# Main.net
KiCad netlist of a schematic drawn in EAGLE
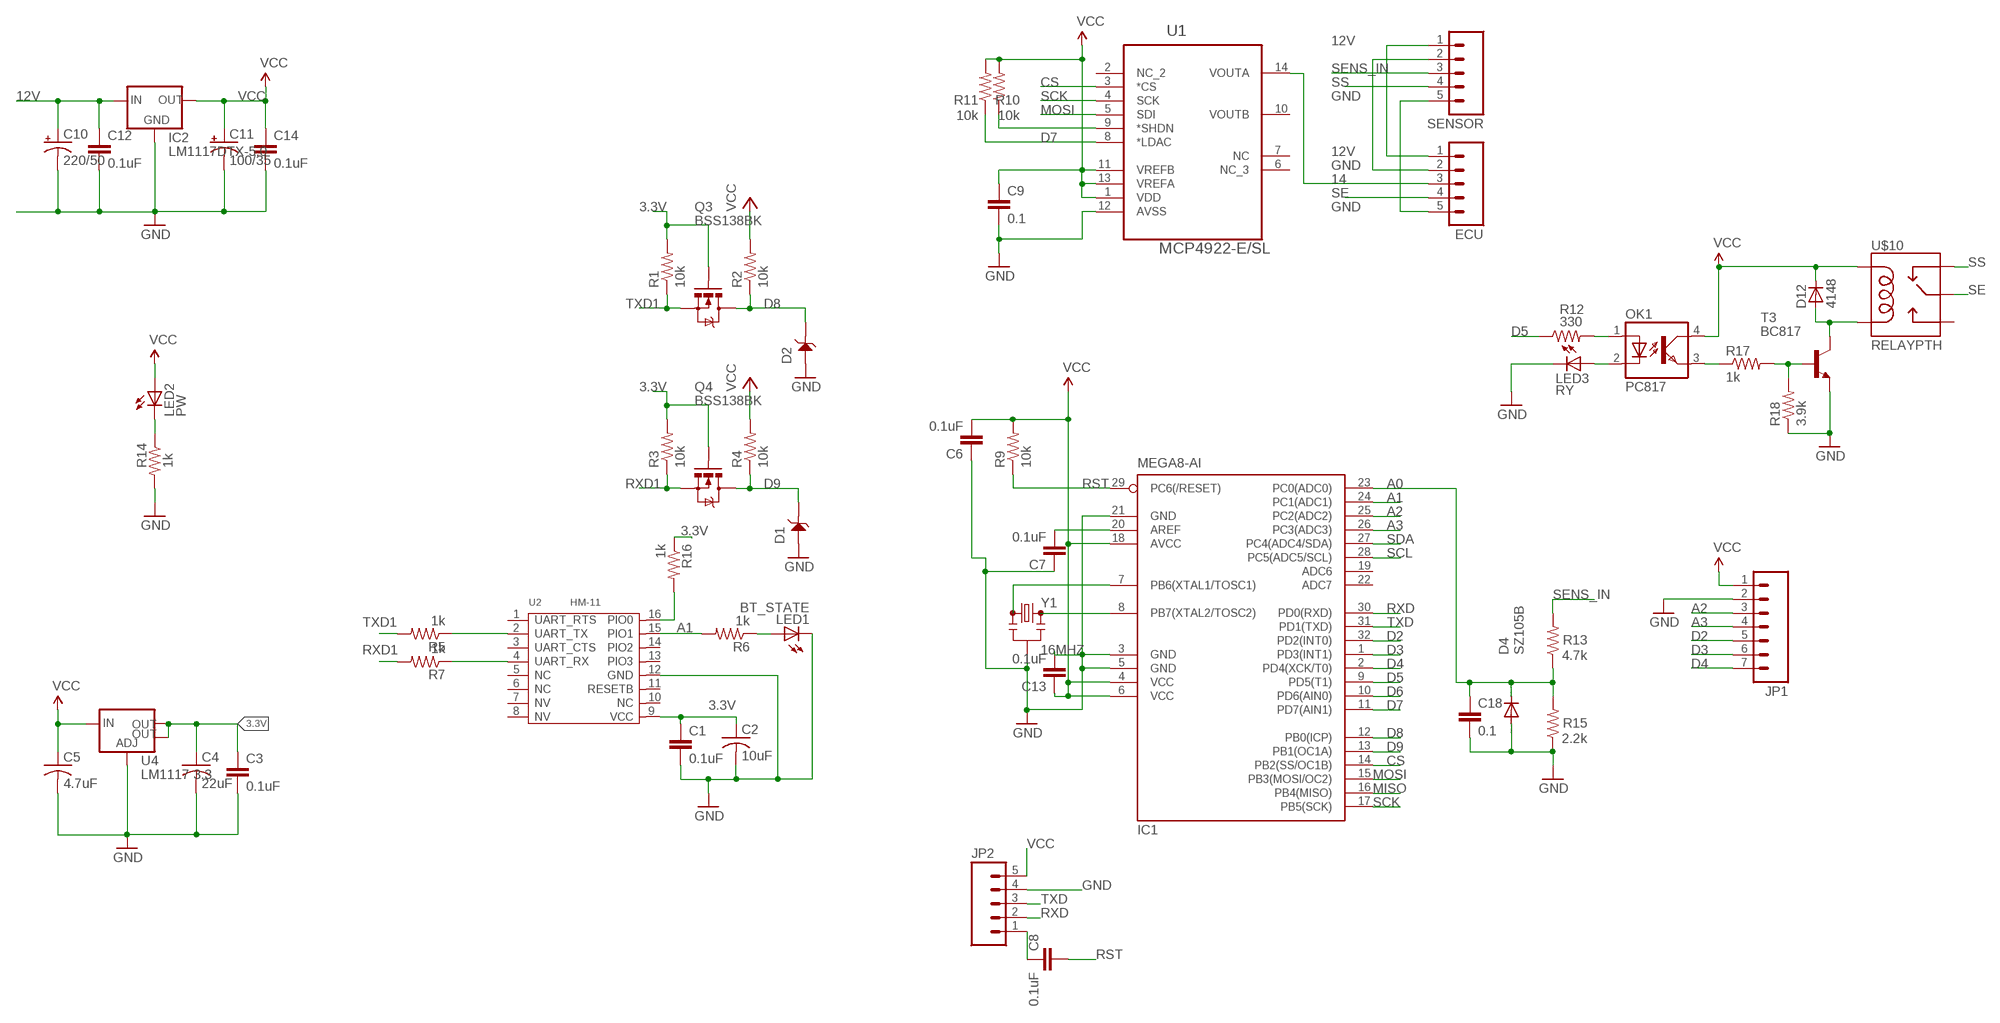
[diagram p0: schematic, sheet 1]

(export (version "E")
  (design (tool "Eeschema 10.0.6"))
  (components
    (comp (ref "C1")
      (value "0.1uF")
      (footprint "eagle-import:0805")
      (libsource (lib "eagle-import") (part "CAP0805"))
    )
    (comp (ref "C2")
      (value "10uF")
      (footprint "eagle-import:C1206")
      (libsource (lib "eagle-import") (part "C-USC1206"))
    )
    (comp (ref "C3")
      (value "0.1uF")
      (footprint "eagle-import:0805")
      (libsource (lib "eagle-import") (part "SparkFun-Passives_CAP0805"))
    )
    (comp (ref "C4")
      (value "22uF")
      (footprint "eagle-import:C1206")
      (libsource (lib "eagle-import") (part "C-USC1206"))
    )
    (comp (ref "C5")
      (value "4.7uF")
      (footprint "eagle-import:C1206")
      (libsource (lib "eagle-import") (part "C-USC1206"))
    )
    (comp (ref "C6")
      (value "0.1uF")
      (footprint "eagle-import:0805")
      (libsource (lib "eagle-import") (part "SparkFun-Passives_CAP0805"))
    )
    (comp (ref "C7")
      (value "0.1uF")
      (footprint "eagle-import:0805")
      (libsource (lib "eagle-import") (part "SparkFun-Passives_CAP0805"))
    )
    (comp (ref "C8")
      (value "0.1uF")
      (footprint "eagle-import:0805")
      (libsource (lib "eagle-import") (part "SparkFun-Passives_CAP0805"))
    )
    (comp (ref "C9")
      (value "0.1")
      (footprint "eagle-import:0805")
      (libsource (lib "eagle-import") (part "SparkFun-Passives_CAP0805"))
    )
    (comp (ref "C10")
      (value "220/50")
      (footprint "eagle-import:153CLV-1010")
      (libsource (lib "eagle-import") (part "CPOL-US153CLV-1010"))
    )
    (comp (ref "C11")
      (value "100/35")
      (footprint "eagle-import:153CLV-0605")
      (libsource (lib "eagle-import") (part "CPOL-US153CLV-0605"))
    )
    (comp (ref "C12")
      (value "0.1uF")
      (footprint "eagle-import:0805")
      (libsource (lib "eagle-import") (part "SparkFun-Passives_CAP0805"))
    )
    (comp (ref "C13")
      (value "0.1uF")
      (footprint "eagle-import:0805")
      (libsource (lib "eagle-import") (part "SparkFun-Passives_CAP0805"))
    )
    (comp (ref "C14")
      (value "0.1uF")
      (footprint "eagle-import:0805")
      (libsource (lib "eagle-import") (part "SparkFun-Passives_CAP0805"))
    )
    (comp (ref "C18")
      (value "0.1")
      (footprint "eagle-import:0805")
      (libsource (lib "eagle-import") (part "SparkFun-Passives_CAP0805"))
    )
    (comp (ref "D1")
      (value "SMF5.0A")
      (footprint "eagle-import:SOD123-2.7X1.6")
      (libsource (lib "eagle-import") (part "D-ESD-2P'CESD5V0D1'"))
    )
    (comp (ref "D2")
      (value "SMF5.0A")
      (footprint "eagle-import:SOD123-2.7X1.6")
      (libsource (lib "eagle-import") (part "D-ESD-2P'CESD5V0D1'"))
    )
    (comp (ref "D4")
      (value "SZ105B")
      (footprint "eagle-import:DO-214AC")
      (libsource (lib "eagle-import") (part "DIODE-DO-214AC"))
    )
    (comp (ref "D12")
      (value "4148")
      (footprint "eagle-import:SOD80")
      (libsource (lib "eagle-import") (part "D-SOD-80"))
    )
    (comp (ref "ECU")
      (value "M05PTH")
      (footprint "eagle-import:1X05")
      (libsource (lib "eagle-import") (part "M05PTH"))
    )
    (comp (ref "IC1")
      (value "MEGA8-AI")
      (footprint "eagle-import:TQFP32-08")
      (fields (field (name "MPN") "ATMEGA8-16AU"))
      (libsource (lib "eagle-import") (part "MEGA8-AI"))
    )
    (comp (ref "IC2")
      (value "LM1117DTX-5.0")
      (footprint "eagle-import:TO252")
      (libsource (lib "eagle-import") (part "LM1117DTX-3.3"))
    )
    (comp (ref "JP1")
      (value "M07")
      (footprint "eagle-import:1X07")
      (libsource (lib "eagle-import") (part "M07"))
    )
    (comp (ref "JP2")
      (value "M05PTH")
      (footprint "eagle-import:1X05")
      (libsource (lib "eagle-import") (part "M05PTH"))
    )
    (comp (ref "LED1")
      (value "BT_STATE")
      (footprint "eagle-import:LED3MM")
      (libsource (lib "eagle-import") (part "LED3MM"))
    )
    (comp (ref "LED2")
      (value "PW")
      (footprint "eagle-import:LED3MM")
      (libsource (lib "eagle-import") (part "LED3MM"))
    )
    (comp (ref "LED3")
      (value "RY")
      (footprint "eagle-import:LED3MM")
      (libsource (lib "eagle-import") (part "LED3MM"))
    )
    (comp (ref "OK1")
      (value "PC817")
      (footprint "eagle-import:DIL4-SMD")
      (libsource (lib "eagle-import") (part "LTV816S"))
    )
    (comp (ref "Q3")
      (value "BSS138BK")
      (footprint "eagle-import:SOT23-3")
      (libsource (lib "eagle-import") (part "MOSFET-NCHANNELBSS138"))
    )
    (comp (ref "Q4")
      (value "BSS138BK")
      (footprint "eagle-import:SOT23-3")
      (libsource (lib "eagle-import") (part "MOSFET-NCHANNELBSS138"))
    )
    (comp (ref "R1")
      (value "10k")
      (footprint "eagle-import:0805")
      (libsource (lib "eagle-import") (part "SparkFun-Resistors_RESISTOR0805-RES"))
    )
    (comp (ref "R2")
      (value "10k")
      (footprint "eagle-import:0805")
      (libsource (lib "eagle-import") (part "SparkFun-Resistors_RESISTOR0805-RES"))
    )
    (comp (ref "R3")
      (value "10k")
      (footprint "eagle-import:0805")
      (libsource (lib "eagle-import") (part "SparkFun-Resistors_RESISTOR0805-RES"))
    )
    (comp (ref "R4")
      (value "10k")
      (footprint "eagle-import:0805")
      (libsource (lib "eagle-import") (part "SparkFun-Resistors_RESISTOR0805-RES"))
    )
    (comp (ref "R5")
      (value "1k")
      (footprint "eagle-import:0805")
      (libsource (lib "eagle-import") (part "SparkFun-Resistors_RESISTOR0805-RES"))
    )
    (comp (ref "R6")
      (value "1k")
      (footprint "eagle-import:0805")
      (libsource (lib "eagle-import") (part "SparkFun-Resistors_RESISTOR0805-RES"))
    )
    (comp (ref "R7")
      (value "1k")
      (footprint "eagle-import:0805")
      (libsource (lib "eagle-import") (part "SparkFun-Resistors_RESISTOR0805-RES"))
    )
    (comp (ref "R9")
      (value "10k")
      (footprint "eagle-import:0805")
      (libsource (lib "eagle-import") (part "SparkFun-Resistors_RESISTOR0805-RES"))
    )
    (comp (ref "R10")
      (value "10k")
      (footprint "eagle-import:0805")
      (libsource (lib "eagle-import") (part "SparkFun-Resistors_RESISTOR0805-RES"))
    )
    (comp (ref "R11")
      (value "10k")
      (footprint "eagle-import:0805")
      (libsource (lib "eagle-import") (part "SparkFun-Resistors_RESISTOR0805-RES"))
    )
    (comp (ref "R12")
      (value "330")
      (footprint "eagle-import:0805")
      (libsource (lib "eagle-import") (part "RESISTOR0805-RES"))
    )
    (comp (ref "R13")
      (value "4.7k")
      (footprint "eagle-import:0805")
      (libsource (lib "eagle-import") (part "SparkFun-Resistors_RESISTOR0805-RES"))
    )
    (comp (ref "R14")
      (value "1k")
      (footprint "eagle-import:0805")
      (libsource (lib "eagle-import") (part "SparkFun-Resistors_RESISTOR0805-RES"))
    )
    (comp (ref "R15")
      (value "2.2k")
      (footprint "eagle-import:0805")
      (libsource (lib "eagle-import") (part "SparkFun-Resistors_RESISTOR0805-RES"))
    )
    (comp (ref "R16")
      (value "1k")
      (footprint "eagle-import:0805")
      (libsource (lib "eagle-import") (part "SparkFun-Resistors_RESISTOR0805-RES"))
    )
    (comp (ref "R17")
      (value "1k")
      (footprint "eagle-import:0805")
      (libsource (lib "eagle-import") (part "RESISTOR0805-RES"))
    )
    (comp (ref "R18")
      (value "3.9k")
      (footprint "eagle-import:0805")
      (libsource (lib "eagle-import") (part "RESISTOR0805-RES"))
    )
    (comp (ref "SENSOR")
      (value "M05PTH")
      (footprint "eagle-import:1X05")
      (libsource (lib "eagle-import") (part "M05PTH"))
    )
    (comp (ref "T3")
      (value "BC817")
      (footprint "eagle-import:SOT23-BEC")
      (libsource (lib "eagle-import") (part "-NPN-SOT23-BECBC817-16"))
    )
    (comp (ref "U$10")
      (value "RELAYPTH")
      (footprint "eagle-import:SRD-05VDC-SL-C")
      (libsource (lib "eagle-import") (part "RELAYPTH"))
    )
    (comp (ref "U1")
      (value "MCP4922-E/SL")
      (footprint "eagle-import:SOIC127P600X175-14N")
      (libsource (lib "eagle-import") (part "MCP4922-E/SL"))
    )
    (comp (ref "U2")
      (value "HM-11")
      (footprint "eagle-import:16P-18.5X13.5X0.8")
      (libsource (lib "eagle-import") (part "HM-11"))
    )
    (comp (ref "U4")
      (value "LM1117 3.3")
      (footprint "eagle-import:SOT223")
      (libsource (lib "eagle-import") (part "V_REG_LM1117SOT223"))
    )
    (comp (ref "Y1")
      (value "16MHZ")
      (footprint "eagle-import:RESONATOR-SMD")
      (libsource (lib "eagle-import") (part "RESONATOR16MHZ"))
    )
  )
  (nets
    (net (code "1") (name "/12V") (class "Default")
      (node (ref "C10") (pin "+") (pinfunction "+_+") (pintype "passive"))
      (node (ref "C12") (pin "1") (pinfunction "1_1") (pintype "passive"))
      (node (ref "ECU") (pin "1") (pinfunction "1_1") (pintype "passive"))
      (node (ref "IC2") (pin "2") (pinfunction "IN_2") (pintype "input"))
      (node (ref "SENSOR") (pin "1") (pinfunction "1_1") (pintype "passive"))
    )
    (net (code "2") (name "/14") (class "Default")
      (node (ref "ECU") (pin "3") (pinfunction "3_3") (pintype "passive"))
      (node (ref "U1") (pin "14") (pinfunction "VOUTA_14") (pintype "output"))
    )
    (net (code "3") (name "/A0") (class "Default")
      (node (ref "C18") (pin "1") (pinfunction "1_1") (pintype "passive"))
      (node (ref "D4") (pin "C") (pinfunction "C_C") (pintype "passive"))
      (node (ref "IC1") (pin "23") (pinfunction "PC0(ADC0)_23") (pintype "bidirectional"))
      (node (ref "R13") (pin "1") (pinfunction "1_1") (pintype "passive"))
      (node (ref "R15") (pin "2") (pinfunction "2_2") (pintype "passive"))
    )
    (net (code "4") (name "/A1") (class "Default")
      (node (ref "IC1") (pin "24") (pinfunction "PC1(ADC1)_24") (pintype "bidirectional"))
      (node (ref "R6") (pin "2") (pinfunction "2_2") (pintype "passive"))
      (node (ref "U2") (pin "15") (pinfunction "PIO1_15") (pintype "bidirectional"))
    )
    (net (code "5") (name "/A2") (class "Default")
      (node (ref "IC1") (pin "25") (pinfunction "PC2(ADC2)_25") (pintype "bidirectional"))
      (node (ref "JP1") (pin "3") (pinfunction "3_3") (pintype "passive"))
    )
    (net (code "6") (name "/A3") (class "Default")
      (node (ref "IC1") (pin "26") (pinfunction "PC3(ADC3)_26") (pintype "bidirectional"))
      (node (ref "JP1") (pin "4") (pinfunction "4_4") (pintype "passive"))
    )
    (net (code "7") (name "/CS") (class "Default")
      (node (ref "IC1") (pin "14") (pinfunction "PB2(SS/OC1B)_14") (pintype "bidirectional"))
      (node (ref "U1") (pin "3") (pinfunction "*CS_3") (pintype "input"))
    )
    (net (code "8") (name "/D2") (class "Default")
      (node (ref "IC1") (pin "32") (pinfunction "PD2(INT0)_32") (pintype "bidirectional"))
      (node (ref "JP1") (pin "5") (pinfunction "5_5") (pintype "passive"))
    )
    (net (code "9") (name "/D3") (class "Default")
      (node (ref "IC1") (pin "1") (pinfunction "PD3(INT1)_1") (pintype "bidirectional"))
      (node (ref "JP1") (pin "6") (pinfunction "6_6") (pintype "passive"))
    )
    (net (code "10") (name "/D4") (class "Default")
      (node (ref "IC1") (pin "2") (pinfunction "PD4(XCK/T0)_2") (pintype "bidirectional"))
      (node (ref "JP1") (pin "7") (pinfunction "7_7") (pintype "passive"))
    )
    (net (code "11") (name "/D5") (class "Default")
      (node (ref "IC1") (pin "9") (pinfunction "PD5(T1)_9") (pintype "bidirectional"))
      (node (ref "R12") (pin "1") (pinfunction "1_1") (pintype "passive"))
    )
    (net (code "12") (name "/D6") (class "Default")
      (node (ref "IC1") (pin "10") (pinfunction "PD6(AIN0)_10") (pintype "bidirectional"))
    )
    (net (code "13") (name "/D7") (class "Default")
      (node (ref "IC1") (pin "11") (pinfunction "PD7(AIN1)_11") (pintype "bidirectional"))
      (node (ref "R11") (pin "1") (pinfunction "1_1") (pintype "passive"))
      (node (ref "U1") (pin "8") (pinfunction "*LDAC_8") (pintype "input"))
    )
    (net (code "14") (name "/D8") (class "Default")
      (node (ref "D2") (pin "2") (pinfunction "2_2") (pintype "bidirectional"))
      (node (ref "IC1") (pin "12") (pinfunction "PB0(ICP)_12") (pintype "bidirectional"))
      (node (ref "Q3") (pin "3") (pinfunction "D_3") (pintype "passive"))
      (node (ref "R2") (pin "1") (pinfunction "1_1") (pintype "passive"))
    )
    (net (code "15") (name "/D9") (class "Default")
      (node (ref "D1") (pin "2") (pinfunction "2_2") (pintype "bidirectional"))
      (node (ref "IC1") (pin "13") (pinfunction "PB1(OC1A)_13") (pintype "bidirectional"))
      (node (ref "Q4") (pin "3") (pinfunction "D_3") (pintype "passive"))
      (node (ref "R4") (pin "1") (pinfunction "1_1") (pintype "passive"))
    )
    (net (code "16") (name "/MISO") (class "Default")
      (node (ref "IC1") (pin "16") (pinfunction "PB4(MISO)_16") (pintype "bidirectional"))
    )
    (net (code "17") (name "/MOSI") (class "Default")
      (node (ref "IC1") (pin "15") (pinfunction "PB3(MOSI/OC2)_15") (pintype "bidirectional"))
      (node (ref "U1") (pin "5") (pinfunction "SDI_5") (pintype "input"))
    )
    (net (code "18") (name "/RST") (class "Default")
      (node (ref "C8") (pin "2") (pinfunction "2_2") (pintype "passive"))
      (node (ref "IC1") (pin "29") (pinfunction "PC6(/RESET)_29") (pintype "bidirectional"))
      (node (ref "R9") (pin "1") (pinfunction "1_1") (pintype "passive"))
    )
    (net (code "19") (name "/RXD") (class "Default")
      (node (ref "IC1") (pin "30") (pinfunction "PD0(RXD)_30") (pintype "bidirectional"))
      (node (ref "JP2") (pin "2") (pinfunction "2_2") (pintype "passive"))
    )
    (net (code "20") (name "/RXD1") (class "Default")
      (node (ref "Q4") (pin "2") (pinfunction "S_2") (pintype "passive"))
      (node (ref "R3") (pin "1") (pinfunction "1_1") (pintype "passive"))
      (node (ref "R7") (pin "2") (pinfunction "2_2") (pintype "passive"))
    )
    (net (code "21") (name "/SCK") (class "Default")
      (node (ref "IC1") (pin "17") (pinfunction "PB5(SCK)_17") (pintype "bidirectional"))
      (node (ref "U1") (pin "4") (pinfunction "SCK_4") (pintype "input"))
    )
    (net (code "22") (name "/SCL") (class "Default")
      (node (ref "IC1") (pin "28") (pinfunction "PC5(ADC5/SCL)_28") (pintype "bidirectional"))
    )
    (net (code "23") (name "/SDA") (class "Default")
      (node (ref "IC1") (pin "27") (pinfunction "PC4(ADC4/SDA)_27") (pintype "bidirectional"))
    )
    (net (code "24") (name "/SE") (class "Default")
      (node (ref "ECU") (pin "4") (pinfunction "4_4") (pintype "passive"))
      (node (ref "U$10") (pin "SWCOMMON") (pinfunction "SWCOMMON_SWCOMMON") (pintype "bidirectional"))
    )
    (net (code "25") (name "/SENS_IN") (class "Default")
      (node (ref "R13") (pin "2") (pinfunction "2_2") (pintype "passive"))
      (node (ref "SENSOR") (pin "3") (pinfunction "3_3") (pintype "passive"))
    )
    (net (code "26") (name "/SS") (class "Default")
      (node (ref "SENSOR") (pin "4") (pinfunction "4_4") (pintype "passive"))
      (node (ref "U$10") (pin "SWCLOSED") (pinfunction "SWCLOSE_SWCLOSED") (pintype "bidirectional"))
    )
    (net (code "27") (name "/TXD") (class "Default")
      (node (ref "IC1") (pin "31") (pinfunction "PD1(TXD)_31") (pintype "bidirectional"))
      (node (ref "JP2") (pin "3") (pinfunction "3_3") (pintype "passive"))
    )
    (net (code "28") (name "/TXD1") (class "Default")
      (node (ref "Q3") (pin "2") (pinfunction "S_2") (pintype "passive"))
      (node (ref "R1") (pin "1") (pinfunction "1_1") (pintype "passive"))
      (node (ref "R5") (pin "2") (pinfunction "2_2") (pintype "passive"))
    )
    (net (code "29") (name "3.3V") (class "Default")
      (node (ref "C1") (pin "1") (pinfunction "1_1") (pintype "passive"))
      (node (ref "C2") (pin "1") (pinfunction "1_1") (pintype "passive"))
      (node (ref "C3") (pin "1") (pinfunction "1_1") (pintype "passive"))
      (node (ref "C4") (pin "1") (pinfunction "1_1") (pintype "passive"))
      (node (ref "Q3") (pin "1") (pinfunction "G_1") (pintype "passive"))
      (node (ref "Q4") (pin "1") (pinfunction "G_1") (pintype "passive"))
      (node (ref "R1") (pin "2") (pinfunction "2_2") (pintype "passive"))
      (node (ref "R16") (pin "1") (pinfunction "1_1") (pintype "passive"))
      (node (ref "R3") (pin "2") (pinfunction "2_2") (pintype "passive"))
      (node (ref "U2") (pin "9") (pinfunction "VCC_9") (pintype "bidirectional"))
      (node (ref "U4") (pin "2") (pinfunction "OUT_2") (pintype "output"))
      (node (ref "U4") (pin "4") (pinfunction "OUT_4") (pintype "output"))
    )
    (net (code "30") (name "GND") (class "Default")
      (node (ref "C1") (pin "2") (pinfunction "2_2") (pintype "passive"))
      (node (ref "C10") (pin "-") (pinfunction "-_-") (pintype "passive"))
      (node (ref "C11") (pin "-") (pinfunction "-_-") (pintype "passive"))
      (node (ref "C12") (pin "2") (pinfunction "2_2") (pintype "passive"))
      (node (ref "C13") (pin "2") (pinfunction "2_2") (pintype "passive"))
      (node (ref "C14") (pin "2") (pinfunction "2_2") (pintype "passive"))
      (node (ref "C18") (pin "2") (pinfunction "2_2") (pintype "passive"))
      (node (ref "C2") (pin "2") (pinfunction "2_2") (pintype "passive"))
      (node (ref "C3") (pin "2") (pinfunction "2_2") (pintype "passive"))
      (node (ref "C4") (pin "2") (pinfunction "2_2") (pintype "passive"))
      (node (ref "C5") (pin "2") (pinfunction "2_2") (pintype "passive"))
      (node (ref "C6") (pin "1") (pinfunction "1_1") (pintype "passive"))
      (node (ref "C7") (pin "1") (pinfunction "1_1") (pintype "passive"))
      (node (ref "C9") (pin "2") (pinfunction "2_2") (pintype "passive"))
      (node (ref "D1") (pin "1") (pinfunction "1_1") (pintype "bidirectional"))
      (node (ref "D2") (pin "1") (pinfunction "1_1") (pintype "bidirectional"))
      (node (ref "D4") (pin "A") (pinfunction "A_A") (pintype "passive"))
      (node (ref "ECU") (pin "2") (pinfunction "2_2") (pintype "passive"))
      (node (ref "ECU") (pin "5") (pinfunction "5_5") (pintype "passive"))
      (node (ref "IC1") (pin "21") (pinfunction "GND_21") (pintype "power_in"))
      (node (ref "IC1") (pin "3") (pinfunction "GND_3") (pintype "power_in"))
      (node (ref "IC1") (pin "5") (pinfunction "GND_5") (pintype "power_in"))
      (node (ref "IC2") (pin "1") (pinfunction "GND_1") (pintype "input"))
      (node (ref "JP1") (pin "2") (pinfunction "2_2") (pintype "passive"))
      (node (ref "JP2") (pin "4") (pinfunction "4_4") (pintype "passive"))
      (node (ref "LED1") (pin "K") (pinfunction "C_K") (pintype "passive"))
      (node (ref "LED3") (pin "K") (pinfunction "C_K") (pintype "passive"))
      (node (ref "R14") (pin "2") (pinfunction "2_2") (pintype "passive"))
      (node (ref "R15") (pin "1") (pinfunction "1_1") (pintype "passive"))
      (node (ref "R18") (pin "1") (pinfunction "1_1") (pintype "passive"))
      (node (ref "SENSOR") (pin "2") (pinfunction "2_2") (pintype "passive"))
      (node (ref "SENSOR") (pin "5") (pinfunction "5_5") (pintype "passive"))
      (node (ref "T3") (pin "E") (pinfunction "E_E") (pintype "passive"))
      (node (ref "U1") (pin "12") (pinfunction "AVSS_12") (pintype "passive"))
      (node (ref "U2") (pin "12") (pinfunction "GND_12") (pintype "bidirectional"))
      (node (ref "U4") (pin "1") (pinfunction "ADJ_1") (pintype "input"))
      (node (ref "Y1") (pin "2") (pinfunction "2_2") (pintype "passive"))
    )
    (net (code "31") (name "Net-(C8-Pad1)") (class "Default")
      (node (ref "C8") (pin "1") (pinfunction "1_1") (pintype "passive"))
      (node (ref "JP2") (pin "1") (pinfunction "1_1") (pintype "passive"))
    )
    (net (code "32") (name "Net-(D12-A)") (class "Default")
      (node (ref "D12") (pin "2") (pinfunction "A_2") (pintype "passive"))
      (node (ref "T3") (pin "C") (pinfunction "C_C") (pintype "passive"))
      (node (ref "U$10") (pin "COIL0") (pinfunction "COIL0_COIL0") (pintype "bidirectional"))
    )
    (net (code "33") (name "Net-(IC1-AREF)") (class "Default")
      (node (ref "C7") (pin "2") (pinfunction "2_2") (pintype "passive"))
      (node (ref "IC1") (pin "20") (pinfunction "AREF_20") (pintype "passive"))
    )
    (net (code "34") (name "Net-(IC1-PB6(XTAL1{slash}TOSC1))") (class "Default")
      (node (ref "IC1") (pin "7") (pinfunction "PB6(XTAL1/TOSC1)_7") (pintype "bidirectional"))
      (node (ref "Y1") (pin "1") (pinfunction "1_1") (pintype "passive"))
    )
    (net (code "35") (name "Net-(IC1-PB7(XTAL2{slash}TOSC2))") (class "Default")
      (node (ref "IC1") (pin "8") (pinfunction "PB7(XTAL2/TOSC2)_8") (pintype "bidirectional"))
      (node (ref "Y1") (pin "3") (pinfunction "3_3") (pintype "passive"))
    )
    (net (code "36") (name "Net-(LED1-PadA)") (class "Default")
      (node (ref "LED1") (pin "A") (pinfunction "A_A") (pintype "passive"))
      (node (ref "R6") (pin "1") (pinfunction "1_1") (pintype "passive"))
    )
    (net (code "37") (name "Net-(LED2-C)") (class "Default")
      (node (ref "LED2") (pin "K") (pinfunction "C_K") (pintype "passive"))
      (node (ref "R14") (pin "1") (pinfunction "1_1") (pintype "passive"))
    )
    (net (code "38") (name "Net-(OK1-A)") (class "Default")
      (node (ref "OK1") (pin "1") (pinfunction "A_1") (pintype "passive"))
      (node (ref "R12") (pin "2") (pinfunction "2_2") (pintype "passive"))
    )
    (net (code "39") (name "Net-(OK1-C)") (class "Default")
      (node (ref "LED3") (pin "A") (pinfunction "A_A") (pintype "passive"))
      (node (ref "OK1") (pin "2") (pinfunction "C_2") (pintype "passive"))
    )
    (net (code "40") (name "Net-(OK1-EMIT)") (class "Default")
      (node (ref "OK1") (pin "3") (pinfunction "EMIT_3") (pintype "passive"))
      (node (ref "R17") (pin "1") (pinfunction "1_1") (pintype "passive"))
    )
    (net (code "41") (name "Net-(R17-Pad2)") (class "Default")
      (node (ref "R17") (pin "2") (pinfunction "2_2") (pintype "passive"))
      (node (ref "R18") (pin "2") (pinfunction "2_2") (pintype "passive"))
      (node (ref "T3") (pin "B") (pinfunction "B_B") (pintype "passive"))
    )
    (net (code "42") (name "Net-(U1-*SHDN)") (class "Default")
      (node (ref "R10") (pin "1") (pinfunction "1_1") (pintype "passive"))
      (node (ref "U1") (pin "9") (pinfunction "*SHDN_9") (pintype "input"))
    )
    (net (code "43") (name "Net-(U2-PIO0)") (class "Default")
      (node (ref "R16") (pin "2") (pinfunction "2_2") (pintype "passive"))
      (node (ref "U2") (pin "16") (pinfunction "PIO0_16") (pintype "bidirectional"))
    )
    (net (code "44") (name "Net-(U2-UART_RX)") (class "Default")
      (node (ref "R7") (pin "1") (pinfunction "1_1") (pintype "passive"))
      (node (ref "U2") (pin "4") (pinfunction "UART_RX_4") (pintype "bidirectional"))
    )
    (net (code "45") (name "Net-(U2-UART_TX)") (class "Default")
      (node (ref "R5") (pin "1") (pinfunction "1_1") (pintype "passive"))
      (node (ref "U2") (pin "2") (pinfunction "UART_TX_2") (pintype "bidirectional"))
    )
    (net (code "46") (name "VCC") (class "Default")
      (node (ref "C11") (pin "+") (pinfunction "+_+") (pintype "passive"))
      (node (ref "C13") (pin "1") (pinfunction "1_1") (pintype "passive"))
      (node (ref "C14") (pin "1") (pinfunction "1_1") (pintype "passive"))
      (node (ref "C5") (pin "1") (pinfunction "1_1") (pintype "passive"))
      (node (ref "C6") (pin "2") (pinfunction "2_2") (pintype "passive"))
      (node (ref "C9") (pin "1") (pinfunction "1_1") (pintype "passive"))
      (node (ref "D12") (pin "1") (pinfunction "C_1") (pintype "passive"))
      (node (ref "IC1") (pin "18") (pinfunction "AVCC_18") (pintype "power_in"))
      (node (ref "IC1") (pin "4") (pinfunction "VCC_4") (pintype "power_in"))
      (node (ref "IC1") (pin "6") (pinfunction "VCC_6") (pintype "power_in"))
      (node (ref "IC2") (pin "TAB") (pinfunction "OUT_TAB") (pintype "passive"))
      (node (ref "JP1") (pin "1") (pinfunction "1_1") (pintype "passive"))
      (node (ref "JP2") (pin "5") (pinfunction "5_5") (pintype "passive"))
      (node (ref "LED2") (pin "A") (pinfunction "A_A") (pintype "passive"))
      (node (ref "OK1") (pin "4") (pinfunction "COL_4") (pintype "passive"))
      (node (ref "R10") (pin "2") (pinfunction "2_2") (pintype "passive"))
      (node (ref "R11") (pin "2") (pinfunction "2_2") (pintype "passive"))
      (node (ref "R2") (pin "2") (pinfunction "2_2") (pintype "passive"))
      (node (ref "R4") (pin "2") (pinfunction "2_2") (pintype "passive"))
      (node (ref "R9") (pin "2") (pinfunction "2_2") (pintype "passive"))
      (node (ref "U$10") (pin "COIL1") (pinfunction "COIL1_COIL1") (pintype "bidirectional"))
      (node (ref "U1") (pin "1") (pinfunction "VDD_1") (pintype "power_in"))
      (node (ref "U1") (pin "11") (pinfunction "VREFB_11") (pintype "input"))
      (node (ref "U1") (pin "13") (pinfunction "VREFA_13") (pintype "input"))
      (node (ref "U4") (pin "3") (pinfunction "IN_3") (pintype "input"))
    )
    (net (code "47") (name "unconnected-(IC1-ADC6-Pad19)") (class "Default")
      (node (ref "IC1") (pin "19") (pinfunction "ADC6_19") (pintype "bidirectional"))
    )
    (net (code "48") (name "unconnected-(IC1-ADC7-Pad22)") (class "Default")
      (node (ref "IC1") (pin "22") (pinfunction "ADC7_22") (pintype "bidirectional"))
    )
    (net (code "49") (name "unconnected-(U$10-PadSWOPEN)") (class "Default")
      (node (ref "U$10") (pin "SWOPEN") (pinfunction "SWOPEN_SWOPEN") (pintype "bidirectional"))
    )
    (net (code "50") (name "unconnected-(U1-NC-Pad7)") (class "Default")
      (node (ref "U1") (pin "7") (pinfunction "NC_7") (pintype "no_connect"))
    )
    (net (code "51") (name "unconnected-(U1-NC_2-Pad2)") (class "Default")
      (node (ref "U1") (pin "2") (pinfunction "NC_2_2") (pintype "no_connect"))
    )
    (net (code "52") (name "unconnected-(U1-NC_3-Pad6)") (class "Default")
      (node (ref "U1") (pin "6") (pinfunction "NC_3_6") (pintype "no_connect"))
    )
    (net (code "53") (name "unconnected-(U1-VOUTB-Pad10)") (class "Default")
      (node (ref "U1") (pin "10") (pinfunction "VOUTB_10") (pintype "output"))
    )
    (net (code "54") (name "unconnected-(U2-NC-Pad5)") (class "Default")
      (node (ref "U2") (pin "5") (pinfunction "NC_5") (pintype "bidirectional"))
    )
    (net (code "55") (name "unconnected-(U2-NC-Pad6)") (class "Default")
      (node (ref "U2") (pin "6") (pinfunction "NC_6") (pintype "bidirectional"))
    )
    (net (code "56") (name "unconnected-(U2-NC-Pad10)") (class "Default")
      (node (ref "U2") (pin "10") (pinfunction "NC_10") (pintype "bidirectional"))
    )
    (net (code "57") (name "unconnected-(U2-NV-Pad7)") (class "Default")
      (node (ref "U2") (pin "7") (pinfunction "NV_7") (pintype "bidirectional"))
    )
    (net (code "58") (name "unconnected-(U2-NV-Pad8)") (class "Default")
      (node (ref "U2") (pin "8") (pinfunction "NV_8") (pintype "bidirectional"))
    )
    (net (code "59") (name "unconnected-(U2-PIO2-Pad14)") (class "Default")
      (node (ref "U2") (pin "14") (pinfunction "PIO2_14") (pintype "bidirectional"))
    )
    (net (code "60") (name "unconnected-(U2-PIO3-Pad13)") (class "Default")
      (node (ref "U2") (pin "13") (pinfunction "PIO3_13") (pintype "bidirectional"))
    )
    (net (code "61") (name "unconnected-(U2-RESETB-Pad11)") (class "Default")
      (node (ref "U2") (pin "11") (pinfunction "RESETB_11") (pintype "bidirectional"))
    )
    (net (code "62") (name "unconnected-(U2-UART_CTS-Pad3)") (class "Default")
      (node (ref "U2") (pin "3") (pinfunction "UART_CTS_3") (pintype "bidirectional"))
    )
    (net (code "63") (name "unconnected-(U2-UART_RTS-Pad1)") (class "Default")
      (node (ref "U2") (pin "1") (pinfunction "UART_RTS_1") (pintype "bidirectional"))
    )
  )
)
